# power.net
KiCad netlist of a schematic drawn in Altium Designer
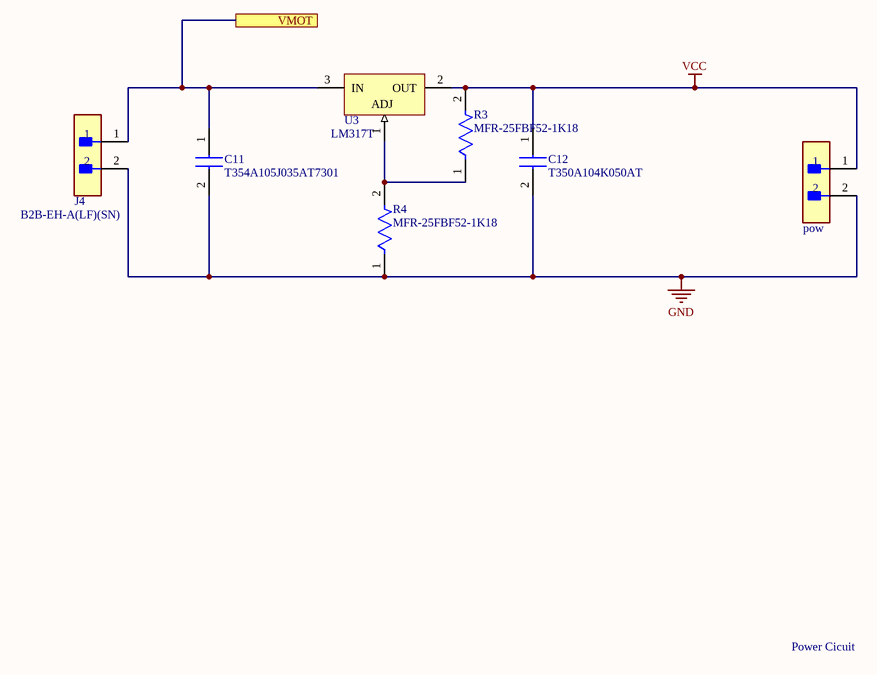
[diagram p0: power.SchDoc]

(export (version "E")
  (design (tool "Eeschema 10.0.6"))
  (components
    (comp (ref "C11")
      (value "T354A105J035AT7301")
      (footprint "SamacSys:T354A105J035AT7301")
      (description "Capacitor")
      (fields (field (name "MOUSER PART NUMBER") "80-T354A105J35AT-TR"))
      (libsource (lib "*") (part "T354A105J035AT7301"))
    )
    (comp (ref "C12")
      (value "T350A104K050AT")
      (footprint "SamacSys:T350A104K050AT")
      (description "Capacitor")
      (fields (field (name "MOUSER PART NUMBER") "80-T350A104K50AT"))
      (libsource (lib "*") (part "T350A104K050AT"))
    )
    (comp (ref "J4")
      (value "B2B-EH-A(LF)(SN)")
      (footprint "FP-B2B-EH-A_LF_SN-MFG")
      (description "CONN HEADER VERT 2POS 2.5MM")
      (libsource (lib "Altium Content Vault") (part "3bc925449376181038e59eaffc5286c"))
    )
    (comp (ref "pow")
      (value "1-TX 2-RX")
      (footprint "FP-M22-2010205-MFG")
      (description "1-SCL\r\n2-SDA")
      (libsource (lib "Altium Content Vault") (part "3bc925449376181038e59eaffc5286c"))
    )
    (comp (ref "R3")
      (value "MFR-25FBF52-1K18")
      (footprint "FP-MFR-25-MFG")
      (description "RES 1.18K OHM 1/4W 1% AXIAL")
      (fields (field (name "MANUFACTURER") "Yageo") (field (name "TOLERANCE") "1%"))
      (libsource (lib "Altium Content Vault") (part "1029c3af85768c4190bb7ad29bc67b5"))
    )
    (comp (ref "R4")
      (value "MFR-25FBF52-1K18")
      (footprint "FP-MFR-25-MFG")
      (description "RES 1.18K OHM 1/4W 1% AXIAL")
      (fields (field (name "MANUFACTURER") "Yageo") (field (name "TOLERANCE") "1%"))
      (libsource (lib "Altium Content Vault") (part "1029c3af85768c4190bb7ad29bc67b5"))
    )
    (comp (ref "U3")
      (value "LM317T")
      (footprint "NDE0003A")
      (description "3-Terminal Adjustable Regulator, 3-pin TO-220")
      (fields (field (name "MANUFACTURER") "Texas Instruments"))
      (libsource (lib "Altium Content Vault") (part "PM-REG-LM1086ADJ-SIL3"))
    )
  )
  (nets
    (net (code "1") (name "/VMOT") (class "Default")
      (node (ref "C11") (pin "1") (pinfunction "+_1") (pintype "passive"))
      (node (ref "J4") (pin "1") (pinfunction "1_1") (pintype "passive"))
      (node (ref "U3") (pin "3") (pinfunction "IN_3") (pintype "power_in"))
    )
    (net (code "2") (name "GND") (class "Default")
      (node (ref "C11") (pin "2") (pinfunction "-_2") (pintype "passive"))
      (node (ref "C12") (pin "2") (pinfunction "2_2") (pintype "passive"))
      (node (ref "J4") (pin "2") (pinfunction "2_2") (pintype "passive"))
      (node (ref "R4") (pin "1") (pinfunction "1_1") (pintype "passive"))
      (node (ref "pow") (pin "2") (pinfunction "2_2") (pintype "passive"))
    )
    (net (code "3") (name "Net-(U3-ADJ)") (class "Default")
      (node (ref "R3") (pin "1") (pinfunction "1_1") (pintype "passive"))
      (node (ref "R4") (pin "2") (pinfunction "2_2") (pintype "passive"))
      (node (ref "U3") (pin "1") (pinfunction "ADJ_1") (pintype "input"))
    )
    (net (code "4") (name "VCC") (class "Default")
      (node (ref "C12") (pin "1") (pinfunction "1_1") (pintype "passive"))
      (node (ref "R3") (pin "2") (pinfunction "2_2") (pintype "passive"))
      (node (ref "U3") (pin "2") (pinfunction "OUT_2") (pintype "power_in"))
      (node (ref "pow") (pin "1") (pinfunction "1_1") (pintype "passive"))
    )
  )
)
